# cnc_shield.net
KiCad netlist of a schematic drawn in EAGLE
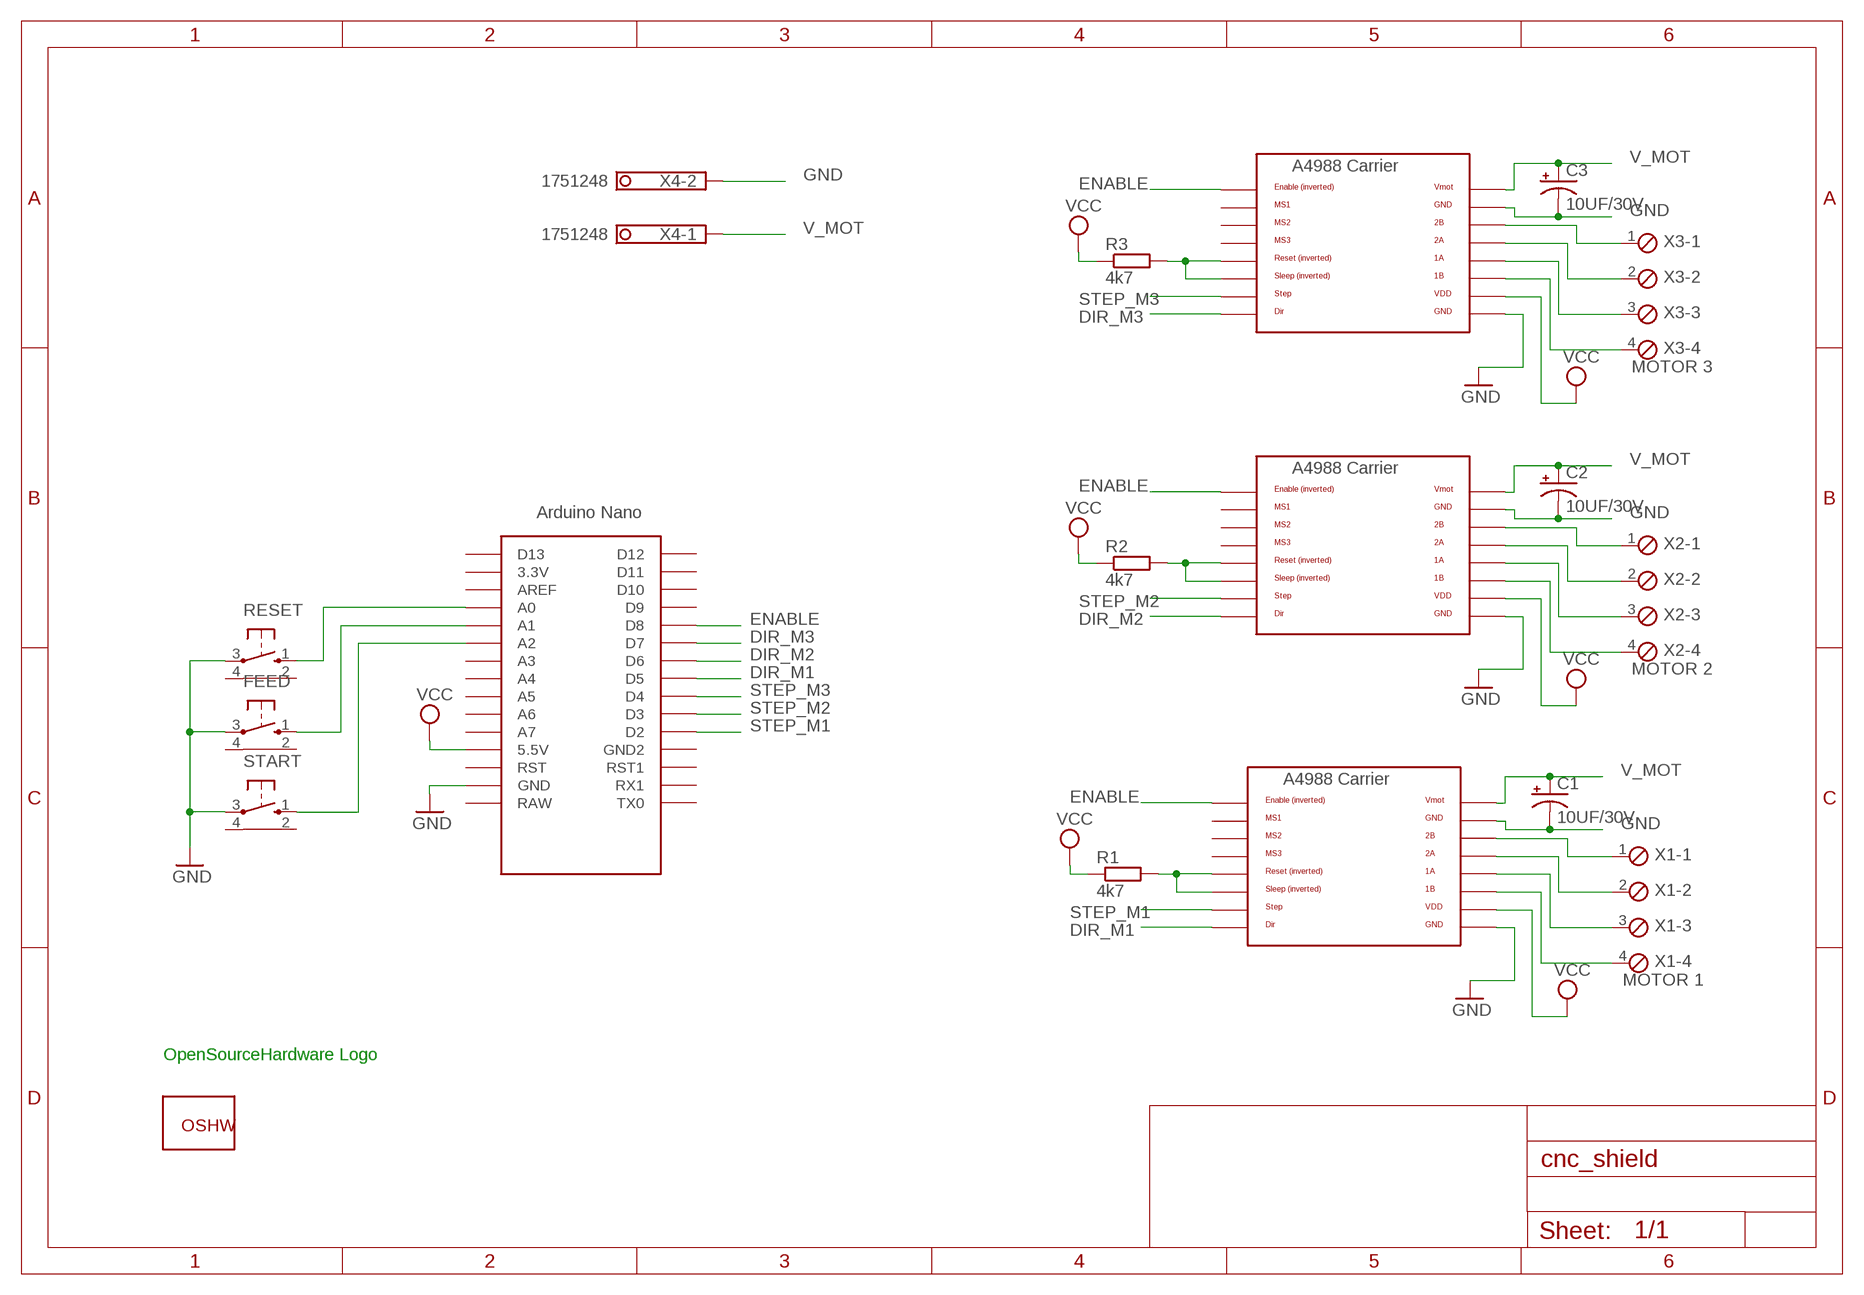
[diagram p0: schematic, sheet 1]

(export (version "E")
  (design (tool "Eeschema 10.0.6"))
  (components
    (comp (ref "C1")
      (value "10UF/30V")
      (footprint "eagle-import:E2,5-6")
      (libsource (lib "eagle-import") (part "CPOL-USE2.5-6"))
    )
    (comp (ref "C2")
      (value "10UF/30V")
      (footprint "eagle-import:E2,5-6")
      (libsource (lib "eagle-import") (part "CPOL-USE2.5-6"))
    )
    (comp (ref "C3")
      (value "10UF/30V")
      (footprint "eagle-import:E2,5-6")
      (libsource (lib "eagle-import") (part "CPOL-USE2.5-6"))
    )
    (comp (ref "FEED")
      (value "10-XX-RPAD")
      (footprint "eagle-import:B3F-10XX-RPAD")
      (libsource (lib "eagle-import") (part "10-XX-RPAD"))
    )
    (comp (ref "GOLD_ORB_SM1")
      (value "OSHWLOGO_GOLD_ORB_SM")
      (footprint "eagle-import:OSHW2")
      (libsource (lib "eagle-import") (part "OSHWLOGO_GOLD_ORB_SM"))
    )
    (comp (ref "R1")
      (value "4k7")
      (footprint "eagle-import:0204_5")
      (libsource (lib "eagle-import") (part "R-EU_0204/5"))
    )
    (comp (ref "R2")
      (value "4k7")
      (footprint "eagle-import:0204_5")
      (libsource (lib "eagle-import") (part "R-EU_0204/5"))
    )
    (comp (ref "R3")
      (value "4k7")
      (footprint "eagle-import:0204_5")
      (libsource (lib "eagle-import") (part "R-EU_0204/5"))
    )
    (comp (ref "RESET")
      (value "10-XX-RPAD")
      (footprint "eagle-import:B3F-10XX-RPAD")
      (libsource (lib "eagle-import") (part "10-XX-RPAD"))
    )
    (comp (ref "START")
      (value "10-XX-RPAD")
      (footprint "eagle-import:B3F-10XX-RPAD")
      (libsource (lib "eagle-import") (part "10-XX-RPAD"))
    )
    (comp (ref "U$1")
      (value "NANO")
      (footprint "eagle-import:NANO")
      (libsource (lib "eagle-import") (part "NANO"))
    )
    (comp (ref "U$2")
      (value "A4988BREAKOUT")
      (footprint "eagle-import:A4988BREAKOUT")
      (libsource (lib "eagle-import") (part "A4988BREAKOUT"))
    )
    (comp (ref "U$3")
      (value "A4988BREAKOUT")
      (footprint "eagle-import:A4988BREAKOUT")
      (libsource (lib "eagle-import") (part "A4988BREAKOUT"))
    )
    (comp (ref "U$4")
      (value "A4988BREAKOUT")
      (footprint "eagle-import:A4988BREAKOUT")
      (libsource (lib "eagle-import") (part "A4988BREAKOUT"))
    )
    (comp (ref "X1")
      (value "MOTOR 1")
      (footprint "eagle-import:4POL254")
      (libsource (lib "eagle-import") (part "MPT4"))
    )
    (comp (ref "X2")
      (value "MOTOR 2")
      (footprint "eagle-import:4POL254")
      (libsource (lib "eagle-import") (part "MPT4"))
    )
    (comp (ref "X3")
      (value "MOTOR 3")
      (footprint "eagle-import:4POL254")
      (libsource (lib "eagle-import") (part "MPT4"))
    )
    (comp (ref "X4")
      (value "1751248")
      (footprint "eagle-import:1751248")
      (libsource (lib "eagle-import") (part "1751248"))
    )
  )
  (nets
    (net (code "1") (name "/DIR_M1") (class "Default")
      (node (ref "U$1") (pin "D5") (pinfunction "D5_D5") (pintype "bidirectional"))
      (node (ref "U$4") (pin "DIR") (pinfunction "DIR_DIR") (pintype "input"))
    )
    (net (code "2") (name "/DIR_M2") (class "Default")
      (node (ref "U$1") (pin "D6") (pinfunction "D6_D6") (pintype "bidirectional"))
      (node (ref "U$2") (pin "DIR") (pinfunction "DIR_DIR") (pintype "input"))
    )
    (net (code "3") (name "/DIR_M3") (class "Default")
      (node (ref "U$1") (pin "D7") (pinfunction "D7_D7") (pintype "bidirectional"))
      (node (ref "U$3") (pin "DIR") (pinfunction "DIR_DIR") (pintype "input"))
    )
    (net (code "4") (name "/ENABLE") (class "Default")
      (node (ref "U$1") (pin "D8") (pinfunction "D8_D8") (pintype "bidirectional"))
      (node (ref "U$2") (pin "EN") (pinfunction "EN_EN") (pintype "input"))
      (node (ref "U$3") (pin "EN") (pinfunction "EN_EN") (pintype "input"))
      (node (ref "U$4") (pin "EN") (pinfunction "EN_EN") (pintype "input"))
    )
    (net (code "5") (name "/STEP_M1") (class "Default")
      (node (ref "U$1") (pin "D2") (pinfunction "D2_D2") (pintype "bidirectional"))
      (node (ref "U$4") (pin "STEP") (pinfunction "STEP_STEP") (pintype "input"))
    )
    (net (code "6") (name "/STEP_M2") (class "Default")
      (node (ref "U$1") (pin "D3") (pinfunction "D3_D3") (pintype "bidirectional"))
      (node (ref "U$2") (pin "STEP") (pinfunction "STEP_STEP") (pintype "input"))
    )
    (net (code "7") (name "/STEP_M3") (class "Default")
      (node (ref "U$1") (pin "D4") (pinfunction "D4_D4") (pintype "bidirectional"))
      (node (ref "U$3") (pin "STEP") (pinfunction "STEP_STEP") (pintype "input"))
    )
    (net (code "8") (name "/V_MOT") (class "Default")
      (node (ref "C1") (pin "+") (pinfunction "+_+") (pintype "passive"))
      (node (ref "C2") (pin "+") (pinfunction "+_+") (pintype "passive"))
      (node (ref "C3") (pin "+") (pinfunction "+_+") (pintype "passive"))
      (node (ref "U$2") (pin "VMOT") (pinfunction "VMOT_VMOT") (pintype "power_in"))
      (node (ref "U$3") (pin "VMOT") (pinfunction "VMOT_VMOT") (pintype "power_in"))
      (node (ref "U$4") (pin "VMOT") (pinfunction "VMOT_VMOT") (pintype "power_in"))
      (node (ref "X4") (pin "1") (pinfunction "K_1") (pintype "passive"))
    )
    (net (code "9") (name "GND") (class "Default")
      (node (ref "C1") (pin "-") (pinfunction "-_-") (pintype "passive"))
      (node (ref "C2") (pin "-") (pinfunction "-_-") (pintype "passive"))
      (node (ref "C3") (pin "-") (pinfunction "-_-") (pintype "passive"))
      (node (ref "FEED") (pin "3") (pinfunction "P_3") (pintype "passive"))
      (node (ref "RESET") (pin "3") (pinfunction "P_3") (pintype "passive"))
      (node (ref "START") (pin "3") (pinfunction "P_3") (pintype "passive"))
      (node (ref "U$1") (pin "GND") (pinfunction "GND_GND") (pintype "bidirectional"))
      (node (ref "U$2") (pin "GND") (pinfunction "GND_GND") (pintype "power_in"))
      (node (ref "U$2") (pin "GND@0") (pinfunction "GND_GND@0") (pintype "power_in"))
      (node (ref "U$3") (pin "GND") (pinfunction "GND_GND") (pintype "power_in"))
      (node (ref "U$3") (pin "GND@0") (pinfunction "GND_GND@0") (pintype "power_in"))
      (node (ref "U$4") (pin "GND") (pinfunction "GND_GND") (pintype "power_in"))
      (node (ref "U$4") (pin "GND@0") (pinfunction "GND_GND@0") (pintype "power_in"))
      (node (ref "X4") (pin "2") (pinfunction "K_2") (pintype "passive"))
    )
    (net (code "10") (name "Net-(FEED-S)") (class "Default")
      (node (ref "FEED") (pin "1") (pinfunction "S_1") (pintype "passive"))
      (node (ref "U$1") (pin "A1") (pinfunction "A1_A1") (pintype "bidirectional"))
    )
    (net (code "11") (name "Net-(RESET-S)") (class "Default")
      (node (ref "RESET") (pin "1") (pinfunction "S_1") (pintype "passive"))
      (node (ref "U$1") (pin "A0") (pinfunction "A0_A0") (pintype "bidirectional"))
    )
    (net (code "12") (name "Net-(START-S)") (class "Default")
      (node (ref "START") (pin "1") (pinfunction "S_1") (pintype "passive"))
      (node (ref "U$1") (pin "A2") (pinfunction "A2_A2") (pintype "bidirectional"))
    )
    (net (code "13") (name "Net-(U$2-Pad2B)") (class "Default")
      (node (ref "U$2") (pin "2B") (pinfunction "2B_2B") (pintype "output"))
      (node (ref "X2") (pin "1") (pinfunction "1_1") (pintype "passive"))
    )
    (net (code "14") (name "Net-(U$2-SLEEP)") (class "Default")
      (node (ref "R2") (pin "2") (pinfunction "2_2") (pintype "passive"))
      (node (ref "U$2") (pin "RST") (pinfunction "RST_RST") (pintype "input"))
      (node (ref "U$2") (pin "SLP") (pinfunction "SLEEP_SLP") (pintype "input"))
    )
    (net (code "15") (name "Net-(U$3-Pad2B)") (class "Default")
      (node (ref "U$3") (pin "2B") (pinfunction "2B_2B") (pintype "output"))
      (node (ref "X3") (pin "1") (pinfunction "1_1") (pintype "passive"))
    )
    (net (code "16") (name "Net-(U$3-SLEEP)") (class "Default")
      (node (ref "R3") (pin "2") (pinfunction "2_2") (pintype "passive"))
      (node (ref "U$3") (pin "RST") (pinfunction "RST_RST") (pintype "input"))
      (node (ref "U$3") (pin "SLP") (pinfunction "SLEEP_SLP") (pintype "input"))
    )
    (net (code "17") (name "Net-(U$4-Pad2B)") (class "Default")
      (node (ref "U$4") (pin "2B") (pinfunction "2B_2B") (pintype "output"))
      (node (ref "X1") (pin "1") (pinfunction "1_1") (pintype "passive"))
    )
    (net (code "18") (name "Net-(U$4-SLEEP)") (class "Default")
      (node (ref "R1") (pin "2") (pinfunction "2_2") (pintype "passive"))
      (node (ref "U$4") (pin "RST") (pinfunction "RST_RST") (pintype "input"))
      (node (ref "U$4") (pin "SLP") (pinfunction "SLEEP_SLP") (pintype "input"))
    )
    (net (code "19") (name "Net-(X1B-1)") (class "Default")
      (node (ref "U$4") (pin "2A") (pinfunction "2A_2A") (pintype "output"))
      (node (ref "X1") (pin "2") (pinfunction "1_2") (pintype "passive"))
    )
    (net (code "20") (name "Net-(X1C-1)") (class "Default")
      (node (ref "U$4") (pin "1A") (pinfunction "1A_1A") (pintype "output"))
      (node (ref "X1") (pin "3") (pinfunction "1_3") (pintype "passive"))
    )
    (net (code "21") (name "Net-(X1D-1)") (class "Default")
      (node (ref "U$4") (pin "1B") (pinfunction "1B_1B") (pintype "output"))
      (node (ref "X1") (pin "4") (pinfunction "1_4") (pintype "passive"))
    )
    (net (code "22") (name "Net-(X2B-1)") (class "Default")
      (node (ref "U$2") (pin "2A") (pinfunction "2A_2A") (pintype "output"))
      (node (ref "X2") (pin "2") (pinfunction "1_2") (pintype "passive"))
    )
    (net (code "23") (name "Net-(X2C-1)") (class "Default")
      (node (ref "U$2") (pin "1A") (pinfunction "1A_1A") (pintype "output"))
      (node (ref "X2") (pin "3") (pinfunction "1_3") (pintype "passive"))
    )
    (net (code "24") (name "Net-(X2D-1)") (class "Default")
      (node (ref "U$2") (pin "1B") (pinfunction "1B_1B") (pintype "output"))
      (node (ref "X2") (pin "4") (pinfunction "1_4") (pintype "passive"))
    )
    (net (code "25") (name "Net-(X3B-1)") (class "Default")
      (node (ref "U$3") (pin "2A") (pinfunction "2A_2A") (pintype "output"))
      (node (ref "X3") (pin "2") (pinfunction "1_2") (pintype "passive"))
    )
    (net (code "26") (name "Net-(X3C-1)") (class "Default")
      (node (ref "U$3") (pin "1A") (pinfunction "1A_1A") (pintype "output"))
      (node (ref "X3") (pin "3") (pinfunction "1_3") (pintype "passive"))
    )
    (net (code "27") (name "Net-(X3D-1)") (class "Default")
      (node (ref "U$3") (pin "1B") (pinfunction "1B_1B") (pintype "output"))
      (node (ref "X3") (pin "4") (pinfunction "1_4") (pintype "passive"))
    )
    (net (code "28") (name "VCC") (class "Default")
      (node (ref "R1") (pin "1") (pinfunction "1_1") (pintype "passive"))
      (node (ref "R2") (pin "1") (pinfunction "1_1") (pintype "passive"))
      (node (ref "R3") (pin "1") (pinfunction "1_1") (pintype "passive"))
      (node (ref "U$1") (pin "5V") (pinfunction "5.5V_5V") (pintype "bidirectional"))
      (node (ref "U$2") (pin "VDD") (pinfunction "VDD_VDD") (pintype "power_in"))
      (node (ref "U$3") (pin "VDD") (pinfunction "VDD_VDD") (pintype "power_in"))
      (node (ref "U$4") (pin "VDD") (pinfunction "VDD_VDD") (pintype "power_in"))
    )
    (net (code "29") (name "unconnected-(FEED-GND1-Pad2)") (class "Default")
      (node (ref "FEED") (pin "2") (pinfunction "GND1_2") (pintype "passive"))
    )
    (net (code "30") (name "unconnected-(FEED-GND2-Pad4)") (class "Default")
      (node (ref "FEED") (pin "4") (pinfunction "GND2_4") (pintype "passive"))
    )
    (net (code "31") (name "unconnected-(RESET-GND1-Pad2)") (class "Default")
      (node (ref "RESET") (pin "2") (pinfunction "GND1_2") (pintype "passive"))
    )
    (net (code "32") (name "unconnected-(RESET-GND2-Pad4)") (class "Default")
      (node (ref "RESET") (pin "4") (pinfunction "GND2_4") (pintype "passive"))
    )
    (net (code "33") (name "unconnected-(START-GND1-Pad2)") (class "Default")
      (node (ref "START") (pin "2") (pinfunction "GND1_2") (pintype "passive"))
    )
    (net (code "34") (name "unconnected-(START-GND2-Pad4)") (class "Default")
      (node (ref "START") (pin "4") (pinfunction "GND2_4") (pintype "passive"))
    )
    (net (code "35") (name "unconnected-(U$1-GND2-PadGND1)") (class "Default")
      (node (ref "U$1") (pin "GND1") (pinfunction "GND2_GND1") (pintype "bidirectional"))
    )
    (net (code "36") (name "unconnected-(U$1-Pad3.3V)") (class "Default")
      (node (ref "U$1") (pin "3.3V") (pinfunction "3.3V_3.3V") (pintype "bidirectional"))
    )
    (net (code "37") (name "unconnected-(U$1-PadA3)") (class "Default")
      (node (ref "U$1") (pin "A3") (pinfunction "A3_A3") (pintype "bidirectional"))
    )
    (net (code "38") (name "unconnected-(U$1-PadA4)") (class "Default")
      (node (ref "U$1") (pin "A4") (pinfunction "A4_A4") (pintype "bidirectional"))
    )
    (net (code "39") (name "unconnected-(U$1-PadA5)") (class "Default")
      (node (ref "U$1") (pin "A5") (pinfunction "A5_A5") (pintype "bidirectional"))
    )
    (net (code "40") (name "unconnected-(U$1-PadA6)") (class "Default")
      (node (ref "U$1") (pin "A6") (pinfunction "A6_A6") (pintype "bidirectional"))
    )
    (net (code "41") (name "unconnected-(U$1-PadA7)") (class "Default")
      (node (ref "U$1") (pin "A7") (pinfunction "A7_A7") (pintype "bidirectional"))
    )
    (net (code "42") (name "unconnected-(U$1-PadAREF)") (class "Default")
      (node (ref "U$1") (pin "AREF") (pinfunction "AREF_AREF") (pintype "bidirectional"))
    )
    (net (code "43") (name "unconnected-(U$1-PadD9)") (class "Default")
      (node (ref "U$1") (pin "D9") (pinfunction "D9_D9") (pintype "bidirectional"))
    )
    (net (code "44") (name "unconnected-(U$1-PadD10)") (class "Default")
      (node (ref "U$1") (pin "D10") (pinfunction "D10_D10") (pintype "bidirectional"))
    )
    (net (code "45") (name "unconnected-(U$1-PadD11)") (class "Default")
      (node (ref "U$1") (pin "D11") (pinfunction "D11_D11") (pintype "bidirectional"))
    )
    (net (code "46") (name "unconnected-(U$1-PadD12)") (class "Default")
      (node (ref "U$1") (pin "D12") (pinfunction "D12_D12") (pintype "bidirectional"))
    )
    (net (code "47") (name "unconnected-(U$1-PadD13)") (class "Default")
      (node (ref "U$1") (pin "D13") (pinfunction "D13_D13") (pintype "bidirectional"))
    )
    (net (code "48") (name "unconnected-(U$1-PadICSP1)") (class "Default")
      (node (ref "U$1") (pin "ICSP1") (pinfunction "ICSP1_ICSP1") (pintype "bidirectional"))
    )
    (net (code "49") (name "unconnected-(U$1-PadICSP2)") (class "Default")
      (node (ref "U$1") (pin "ICSP2") (pinfunction "ICSP2_ICSP2") (pintype "bidirectional"))
    )
    (net (code "50") (name "unconnected-(U$1-PadICSP3)") (class "Default")
      (node (ref "U$1") (pin "ICSP3") (pinfunction "ICSP3_ICSP3") (pintype "bidirectional"))
    )
    (net (code "51") (name "unconnected-(U$1-PadICSP4)") (class "Default")
      (node (ref "U$1") (pin "ICSP4") (pinfunction "ICSP4_ICSP4") (pintype "bidirectional"))
    )
    (net (code "52") (name "unconnected-(U$1-PadICSP5)") (class "Default")
      (node (ref "U$1") (pin "ICSP5") (pinfunction "ICSP5_ICSP5") (pintype "bidirectional"))
    )
    (net (code "53") (name "unconnected-(U$1-PadICSP6)") (class "Default")
      (node (ref "U$1") (pin "ICSP6") (pinfunction "ICSP6_ICSP6") (pintype "bidirectional"))
    )
    (net (code "54") (name "unconnected-(U$1-PadRAW)") (class "Default")
      (node (ref "U$1") (pin "RAW") (pinfunction "RAW_RAW") (pintype "bidirectional"))
    )
    (net (code "55") (name "unconnected-(U$1-PadRST)") (class "Default")
      (node (ref "U$1") (pin "RST") (pinfunction "RST_RST") (pintype "bidirectional"))
    )
    (net (code "56") (name "unconnected-(U$1-PadRST1)") (class "Default")
      (node (ref "U$1") (pin "RST1") (pinfunction "RST1_RST1") (pintype "bidirectional"))
    )
    (net (code "57") (name "unconnected-(U$1-PadRX1)") (class "Default")
      (node (ref "U$1") (pin "RX1") (pinfunction "RX1_RX1") (pintype "bidirectional"))
    )
    (net (code "58") (name "unconnected-(U$1-PadTX0)") (class "Default")
      (node (ref "U$1") (pin "TX0") (pinfunction "TX0_TX0") (pintype "bidirectional"))
    )
    (net (code "59") (name "unconnected-(U$2-PadMS1)") (class "Default")
      (node (ref "U$2") (pin "MS1") (pinfunction "MS1_MS1") (pintype "input"))
    )
    (net (code "60") (name "unconnected-(U$2-PadMS2)") (class "Default")
      (node (ref "U$2") (pin "MS2") (pinfunction "MS2_MS2") (pintype "input"))
    )
    (net (code "61") (name "unconnected-(U$2-PadMS3)") (class "Default")
      (node (ref "U$2") (pin "MS3") (pinfunction "MS3_MS3") (pintype "input"))
    )
    (net (code "62") (name "unconnected-(U$3-PadMS1)") (class "Default")
      (node (ref "U$3") (pin "MS1") (pinfunction "MS1_MS1") (pintype "input"))
    )
    (net (code "63") (name "unconnected-(U$3-PadMS2)") (class "Default")
      (node (ref "U$3") (pin "MS2") (pinfunction "MS2_MS2") (pintype "input"))
    )
    (net (code "64") (name "unconnected-(U$3-PadMS3)") (class "Default")
      (node (ref "U$3") (pin "MS3") (pinfunction "MS3_MS3") (pintype "input"))
    )
    (net (code "65") (name "unconnected-(U$4-PadMS1)") (class "Default")
      (node (ref "U$4") (pin "MS1") (pinfunction "MS1_MS1") (pintype "input"))
    )
    (net (code "66") (name "unconnected-(U$4-PadMS2)") (class "Default")
      (node (ref "U$4") (pin "MS2") (pinfunction "MS2_MS2") (pintype "input"))
    )
    (net (code "67") (name "unconnected-(U$4-PadMS3)") (class "Default")
      (node (ref "U$4") (pin "MS3") (pinfunction "MS3_MS3") (pintype "input"))
    )
  )
)
